# C-10_PMIC.net
KiCad netlist of a schematic drawn in Altium Designer
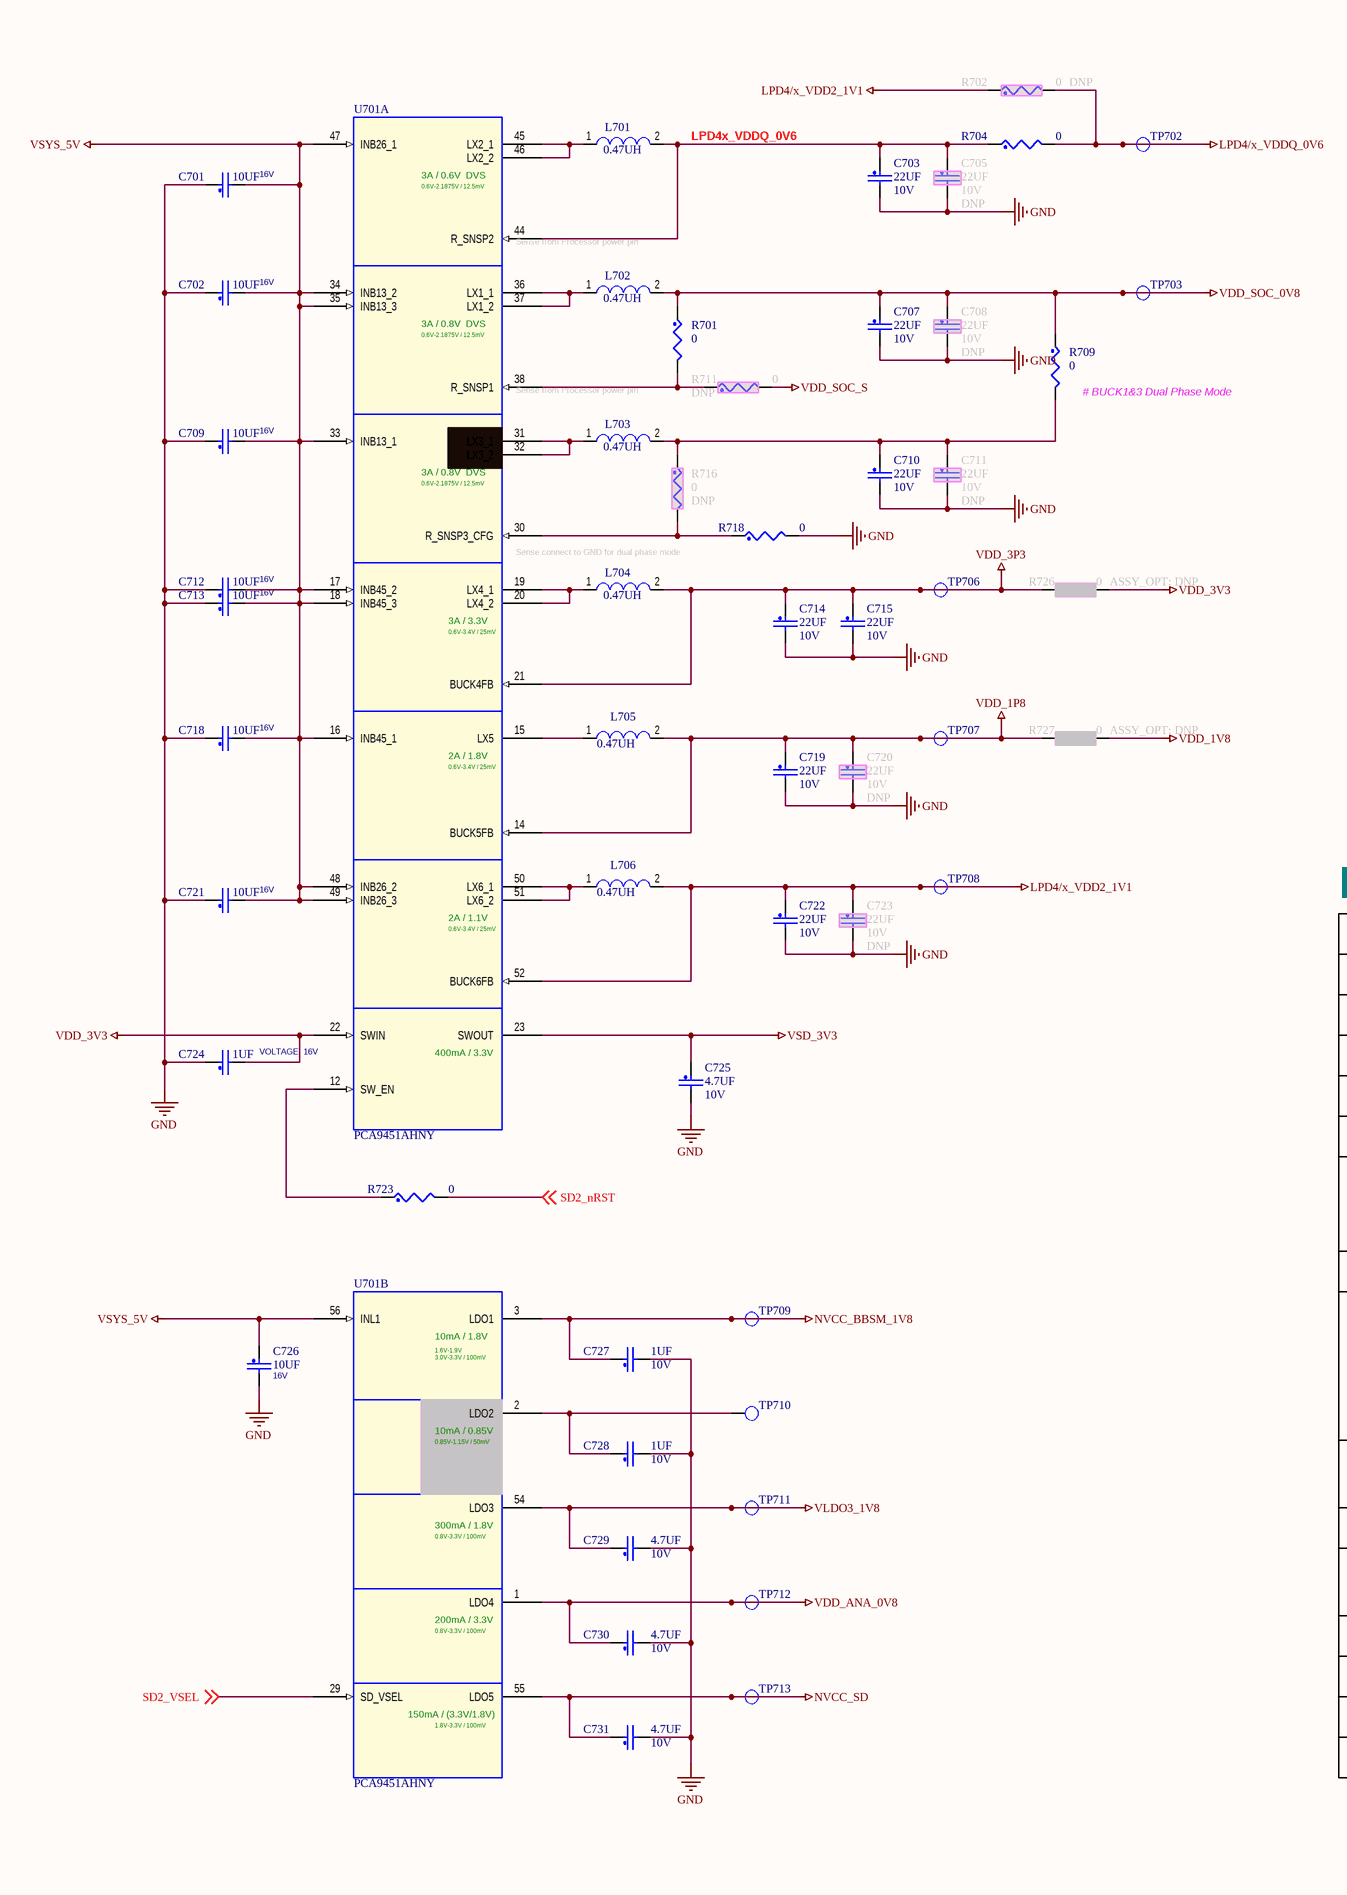
[diagram p0: C-10 PMIC.SchDoc, left]
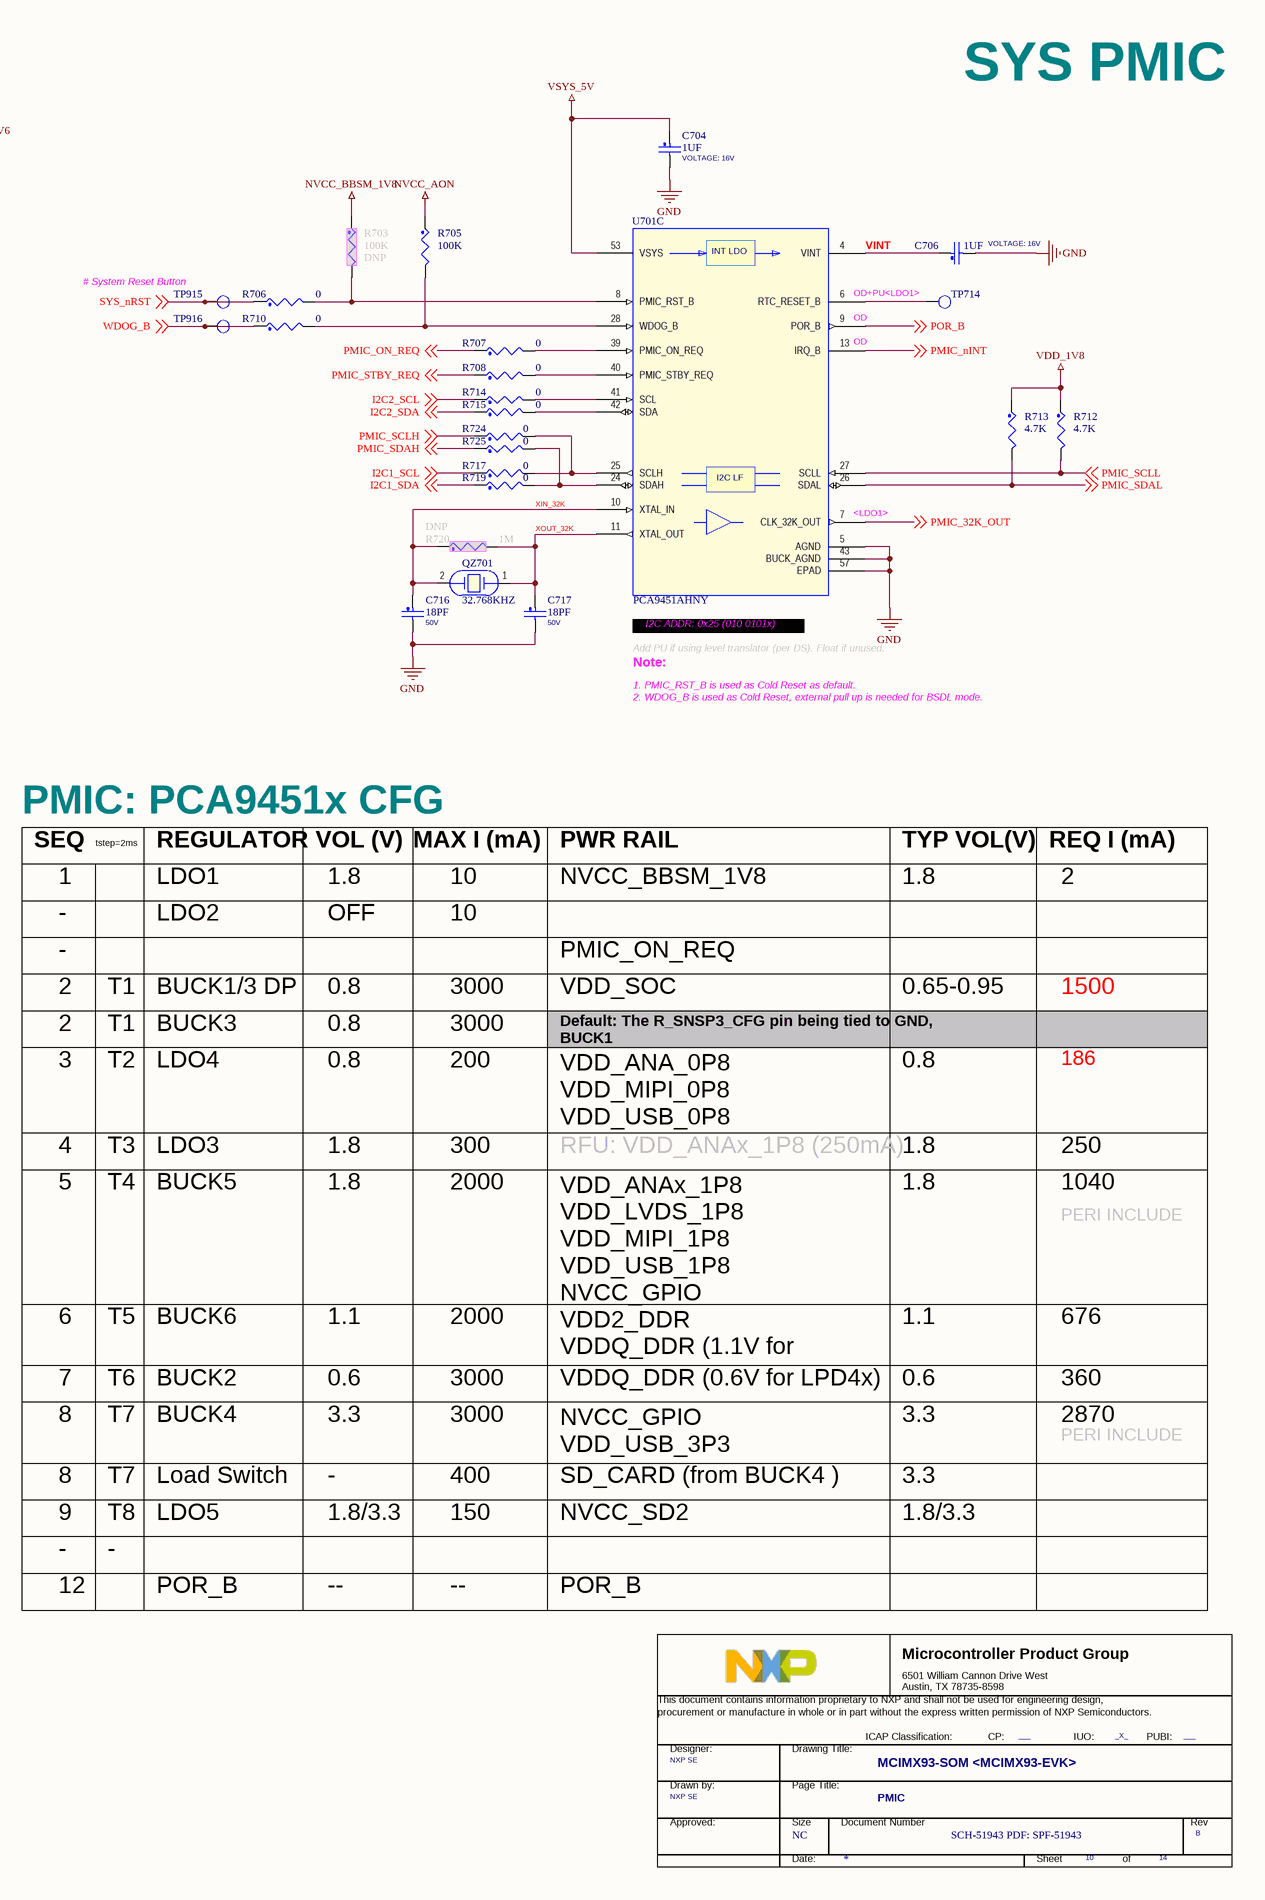
[diagram p1: C-10 PMIC.SchDoc, right]

(export (version "E")
  (design (tool "Eeschema 10.0.6"))
  (components
    (comp (ref "C701")
      (value "10UF")
      (footprint "CC0603")
      (description "CAP CER 10.0uF 16V 10% X5R 0603")
      (fields (field (name "TOLERANCE") "10%") (field (name "VOLTAGE") "16V"))
      (libsource (lib "*") (part "CAP_NP"))
    )
    (comp (ref "C702")
      (value "10UF")
      (footprint "CC0603")
      (description "CAP CER 10.0uF 16V 10% X5R 0603")
      (fields (field (name "VOLTAGE") "16V") (field (name "TOLERANCE") "10%"))
      (libsource (lib "*") (part "CAP_NP"))
    )
    (comp (ref "C703")
      (value "22UF")
      (footprint "CC0603")
      (description "CAP CER 22uF 10V 20% X5R 0603")
      (fields (field (name "VOLTAGE") "10V") (field (name "TOLERANCE") "20%"))
      (libsource (lib "*") (part "CAP_NP"))
    )
    (comp (ref "C704")
      (value "1UF")
      (footprint "0402_CC")
      (description "CAP CER 1uF 16V 10% X5R 0402")
      (fields (field (name "TOLERANCE") "10%") (field (name "VOLTAGE") "16V"))
      (libsource (lib "*") (part "CAP_NP"))
    )
    (comp (ref "C705")
      (value "22UF")
      (footprint "CC0603")
      (description "CAP CER 22uF 10V 20% X5R 0603")
      (fields (field (name "ASSY_OPT") "DNP") (field (name "TOLERANCE") "20%") (field (name "VOLTAGE") "10V"))
      (libsource (lib "*") (part "CAP_NP"))
    )
    (comp (ref "C706")
      (value "1UF")
      (footprint "0402_CC")
      (description "CAP CER 1uF 16V 10% X5R 0402")
      (fields (field (name "VOLTAGE") "16V") (field (name "TOLERANCE") "10%"))
      (libsource (lib "*") (part "CAP_NP"))
    )
    (comp (ref "C707")
      (value "22UF")
      (footprint "CC0603")
      (description "CAP CER 22uF 10V 20% X5R 0603")
      (fields (field (name "TOLERANCE") "20%") (field (name "VOLTAGE") "10V"))
      (libsource (lib "*") (part "CAP_NP"))
    )
    (comp (ref "C708")
      (value "22UF")
      (footprint "CC0603")
      (description "CAP CER 22uF 10V 20% X5R 0603")
      (fields (field (name "ASSY_OPT") "DNP") (field (name "VOLTAGE") "10V") (field (name "TOLERANCE") "20%"))
      (libsource (lib "*") (part "CAP_NP"))
    )
    (comp (ref "C709")
      (value "10UF")
      (footprint "CC0603")
      (description "CAP CER 10.0uF 16V 10% X5R 0603")
      (fields (field (name "VOLTAGE") "16V") (field (name "TOLERANCE") "10%"))
      (libsource (lib "*") (part "CAP_NP"))
    )
    (comp (ref "C710")
      (value "22UF")
      (footprint "CC0603")
      (description "CAP CER 22uF 10V 20% X5R 0603")
      (fields (field (name "VOLTAGE") "10V") (field (name "TOLERANCE") "20%"))
      (libsource (lib "*") (part "CAP_NP"))
    )
    (comp (ref "C711")
      (value "22UF")
      (footprint "CC0603")
      (description "CAP CER 22uF 10V 20% X5R 0603")
      (fields (field (name "ASSY_OPT") "DNP") (field (name "TOLERANCE") "20%") (field (name "VOLTAGE") "10V"))
      (libsource (lib "*") (part "CAP_NP"))
    )
    (comp (ref "C712")
      (value "10UF")
      (footprint "CC0603")
      (description "CAP CER 10.0uF 16V 10% X5R 0603")
      (fields (field (name "TOLERANCE") "10%") (field (name "VOLTAGE") "16V"))
      (libsource (lib "*") (part "CAP_NP"))
    )
    (comp (ref "C713")
      (value "10UF")
      (footprint "CC0603")
      (description "CAP CER 10.0uF 16V 10% X5R 0603")
      (fields (field (name "VOLTAGE") "16V") (field (name "TOLERANCE") "10%"))
      (libsource (lib "*") (part "CAP_NP"))
    )
    (comp (ref "C714")
      (value "22UF")
      (footprint "CC0603")
      (description "CAP CER 22uF 10V 20% X5R 0603")
      (fields (field (name "VOLTAGE") "10V") (field (name "TOLERANCE") "20%"))
      (libsource (lib "*") (part "CAP_NP"))
    )
    (comp (ref "C715")
      (value "22UF")
      (footprint "CC0603")
      (description "CAP CER 22uF 10V 20% X5R 0603")
      (fields (field (name "VOLTAGE") "10V") (field (name "TOLERANCE") "20%"))
      (libsource (lib "*") (part "CAP_NP"))
    )
    (comp (ref "C716")
      (value "18PF")
      (footprint "0201_CC")
      (description "CAP CER 18pF 50V 5% C0G 0201")
      (fields (field (name "TOLERANCE") "5%") (field (name "VOLTAGE") "50V"))
      (libsource (lib "*") (part "CAP_NP"))
    )
    (comp (ref "C717")
      (value "18PF")
      (footprint "0201_CC")
      (description "CAP CER 18pF 50V 5% C0G 0201")
      (fields (field (name "TOLERANCE") "5%") (field (name "VOLTAGE") "50V"))
      (libsource (lib "*") (part "CAP_NP"))
    )
    (comp (ref "C718")
      (value "10UF")
      (footprint "CC0603")
      (description "CAP CER 10.0uF 16V 10% X5R 0603")
      (fields (field (name "TOLERANCE") "10%") (field (name "VOLTAGE") "16V"))
      (libsource (lib "*") (part "CAP_NP"))
    )
    (comp (ref "C719")
      (value "22UF")
      (footprint "CC0603")
      (description "CAP CER 22uF 10V 20% X5R 0603")
      (fields (field (name "VOLTAGE") "10V") (field (name "TOLERANCE") "20%"))
      (libsource (lib "*") (part "CAP_NP"))
    )
    (comp (ref "C720")
      (value "22UF")
      (footprint "CC0603")
      (description "CAP CER 22uF 10V 20% X5R 0603")
      (fields (field (name "ASSY_OPT") "DNP") (field (name "VOLTAGE") "10V") (field (name "TOLERANCE") "20%"))
      (libsource (lib "*") (part "CAP_NP"))
    )
    (comp (ref "C721")
      (value "10UF")
      (footprint "CC0603")
      (description "CAP CER 10.0uF 16V 10% X5R 0603")
      (fields (field (name "TOLERANCE") "10%") (field (name "VOLTAGE") "16V"))
      (libsource (lib "*") (part "CAP_NP"))
    )
    (comp (ref "C722")
      (value "22UF")
      (footprint "CC0603")
      (description "CAP CER 22uF 10V 20% X5R 0603")
      (fields (field (name "VOLTAGE") "10V") (field (name "TOLERANCE") "20%"))
      (libsource (lib "*") (part "CAP_NP"))
    )
    (comp (ref "C723")
      (value "22UF")
      (footprint "CC0603")
      (description "CAP CER 22uF 10V 20% X5R 0603")
      (fields (field (name "ASSY_OPT") "DNP") (field (name "TOLERANCE") "20%") (field (name "VOLTAGE") "10V"))
      (libsource (lib "*") (part "CAP_NP"))
    )
    (comp (ref "C724")
      (value "1UF")
      (footprint "0402_CC")
      (description "CAP CER 1uF 16V 10% X5R 0402")
      (fields (field (name "TOLERANCE") "10%") (field (name "VOLTAGE") "16V"))
      (libsource (lib "*") (part "CAP_NP"))
    )
    (comp (ref "C725")
      (value "4.7UF")
      (footprint "cc0402_tol0p15")
      (description "CAP CER 4.7uF 10V 10% X5R 0402")
      (fields (field (name "TOLERANCE") "10%") (field (name "VOLTAGE") "10V"))
      (libsource (lib "*") (part "CAP_NP"))
    )
    (comp (ref "C726")
      (value "10UF")
      (footprint "CC0603")
      (description "CAP CER 10.0uF 16V 10% X5R 0603")
      (fields (field (name "TOLERANCE") "10%") (field (name "VOLTAGE") "16V"))
      (libsource (lib "*") (part "CAP_NP"))
    )
    (comp (ref "C727")
      (value "1UF")
      (footprint "0201_CC")
      (description "CAP CER 1.0uF 10V 10% X5R 0201")
      (fields (field (name "VOLTAGE") "10V") (field (name "TOLERANCE") "10%"))
      (libsource (lib "*") (part "CAP_NP"))
    )
    (comp (ref "C728")
      (value "1UF")
      (footprint "0201_CC")
      (description "CAP CER 1.0uF 10V 10% X5R 0201")
      (fields (field (name "VOLTAGE") "10V") (field (name "TOLERANCE") "10%"))
      (libsource (lib "*") (part "CAP_NP"))
    )
    (comp (ref "C729")
      (value "4.7UF")
      (footprint "cc0402_tol0p15")
      (description "CAP CER 4.7uF 10V 10% X5R 0402")
      (fields (field (name "VOLTAGE") "10V") (field (name "TOLERANCE") "10%"))
      (libsource (lib "*") (part "CAP_NP"))
    )
    (comp (ref "C730")
      (value "4.7UF")
      (footprint "cc0402_tol0p15")
      (description "CAP CER 4.7uF 10V 10% X5R 0402")
      (fields (field (name "VOLTAGE") "10V") (field (name "TOLERANCE") "10%"))
      (libsource (lib "*") (part "CAP_NP"))
    )
    (comp (ref "C731")
      (value "4.7UF")
      (footprint "cc0402_tol0p15")
      (description "CAP CER 4.7uF 10V 10% X5R 0402")
      (fields (field (name "VOLTAGE") "10V") (field (name "TOLERANCE") "10%"))
      (libsource (lib "*") (part "CAP_NP"))
    )
    (comp (ref "L701")
      (value "0.47UH")
      (footprint "ind_sph2520")
      (description "IND PWR 0.47uH@1MHZ 4.7A 20% SMT")
      (fields (field (name "TOLERANCE") "20%"))
      (libsource (lib "*") (part "INDUCTOR"))
    )
    (comp (ref "L702")
      (value "0.47UH")
      (footprint "ind_sph2520")
      (description "IND PWR 0.47uH@1MHZ 4.7A 20% SMT")
      (fields (field (name "TOLERANCE") "20%"))
      (libsource (lib "*") (part "INDUCTOR"))
    )
    (comp (ref "L703")
      (value "0.47UH")
      (footprint "ind_sph2520")
      (description "IND PWR 0.47uH@1MHZ 4.7A 20% SMT")
      (fields (field (name "TOLERANCE") "20%"))
      (libsource (lib "*") (part "INDUCTOR"))
    )
    (comp (ref "L704")
      (value "0.47UH")
      (footprint "ind_sph2520")
      (description "IND PWR 0.47uH@1MHZ 4.7A 20% SMT")
      (fields (field (name "TOLERANCE") "20%"))
      (libsource (lib "*") (part "INDUCTOR"))
    )
    (comp (ref "L705")
      (value "0.47UH")
      (footprint "IND_2016A")
      (description "IND PWR 0.47uH@1MHz 3.4A 20% 2016")
      (fields (field (name "TOLERANCE") "20%"))
      (libsource (lib "*") (part "INDUCTOR"))
    )
    (comp (ref "L706")
      (value "0.47UH")
      (footprint "IND_2016A")
      (description "IND PWR 0.47uH@1MHz 3.4A 20% 2016")
      (fields (field (name "TOLERANCE") "20%"))
      (libsource (lib "*") (part "INDUCTOR"))
    )
    (comp (ref "QZ701")
      (value "32.768KHZ")
      (footprint "XTAL2-3P2X1P5-SM")
      (description "XTAL 32.768KHZ 12.5PF 20PPM 3.2X1.5MM SMT")
      (libsource (lib "*") (part "XTAL"))
    )
    (comp (ref "R701")
      (value "0")
      (footprint "0402_CC")
      (description "RES MF ZERO OHM 1/16W 5% 0402")
      (fields (field (name "VOLTAGE") "1/16W") (field (name "TOLERANCE") "5%"))
      (libsource (lib "*") (part "RES"))
    )
    (comp (ref "R702")
      (value "0")
      (footprint "0603_CC")
      (description "RES MF ZERO OHM 1/10W -- 0603")
      (fields (field (name "ASSY_OPT") "DNP"))
      (libsource (lib "*") (part "RES"))
    )
    (comp (ref "R703")
      (value "100K")
      (footprint "0402_CC")
      (description "RES MF 100K 1/16W 5% 0402")
      (fields (field (name "ASSY_OPT") "DNP") (field (name "TOLERANCE") "5%") (field (name "VOLTAGE") "50V"))
      (libsource (lib "*") (part "RES"))
    )
    (comp (ref "R704")
      (value "0")
      (footprint "0603_CC")
      (description "RES MF ZERO OHM 1/10W -- 0603")
      (libsource (lib "*") (part "RES"))
    )
    (comp (ref "R705")
      (value "100K")
      (footprint "0402_CC")
      (description "RES MF 100K 1/16W 5% 0402")
      (fields (field (name "VOLTAGE") "50V") (field (name "TOLERANCE") "5%"))
      (libsource (lib "*") (part "RES"))
    )
    (comp (ref "R706")
      (value "0")
      (footprint "0402_CC")
      (description "RES MF ZERO OHM 1/16W 5% 0402")
      (fields (field (name "VOLTAGE") "1/16W") (field (name "TOLERANCE") "5%"))
      (libsource (lib "*") (part "RES"))
    )
    (comp (ref "R707")
      (value "0")
      (footprint "0402_CC")
      (description "RES MF ZERO OHM 1/16W 5% 0402")
      (fields (field (name "TOLERANCE") "5%") (field (name "VOLTAGE") "1/16W"))
      (libsource (lib "*") (part "RES"))
    )
    (comp (ref "R708")
      (value "0")
      (footprint "0402_CC")
      (description "RES MF ZERO OHM 1/16W 5% 0402")
      (fields (field (name "VOLTAGE") "1/16W") (field (name "TOLERANCE") "5%"))
      (libsource (lib "*") (part "RES"))
    )
    (comp (ref "R709")
      (value "0")
      (footprint "0603_CC")
      (description "RES MF ZERO OHM 1/10W -- 0603")
      (libsource (lib "*") (part "RES"))
    )
    (comp (ref "R710")
      (value "0")
      (footprint "0402_CC")
      (description "RES MF ZERO OHM 1/16W 5% 0402")
      (fields (field (name "VOLTAGE") "1/16W") (field (name "TOLERANCE") "5%"))
      (libsource (lib "*") (part "RES"))
    )
    (comp (ref "R711")
      (value "0")
      (footprint "0402_CC")
      (description "RES MF ZERO OHM 1/16W 5% 0402")
      (fields
        (field (name "ASSY_OPT") "DNP")
        (field (name "TOLERANCE") "5%")
        (field (name "VOLTAGE") "1/16W")
      )
      (libsource (lib "*") (part "RES"))
    )
    (comp (ref "R712")
      (value "4.7K")
      (footprint "0402_CC")
      (description "RES MF 4.7K 1/10W 5% AEC-Q200 0402")
      (fields (field (name "TOLERANCE") "5%") (field (name "VOLTAGE") "50V"))
      (libsource (lib "*") (part "RES"))
    )
    (comp (ref "R713")
      (value "4.7K")
      (footprint "0402_CC")
      (description "RES MF 4.7K 1/10W 5% AEC-Q200 0402")
      (fields (field (name "VOLTAGE") "50V") (field (name "TOLERANCE") "5%"))
      (libsource (lib "*") (part "RES"))
    )
    (comp (ref "R714")
      (value "0")
      (footprint "0402_CC")
      (description "RES MF ZERO OHM 1/16W 5% 0402")
      (fields (field (name "TOLERANCE") "5%") (field (name "VOLTAGE") "1/16W"))
      (libsource (lib "*") (part "RES"))
    )
    (comp (ref "R715")
      (value "0")
      (footprint "0402_CC")
      (description "RES MF ZERO OHM 1/16W 5% 0402")
      (fields (field (name "TOLERANCE") "5%") (field (name "VOLTAGE") "1/16W"))
      (libsource (lib "*") (part "RES"))
    )
    (comp (ref "R716")
      (value "0")
      (footprint "0402_CC")
      (description "RES MF ZERO OHM 1/16W 5% 0402")
      (fields
        (field (name "ASSY_OPT") "DNP")
        (field (name "TOLERANCE") "5%")
        (field (name "VOLTAGE") "1/16W")
      )
      (libsource (lib "*") (part "RES"))
    )
    (comp (ref "R717")
      (value "0")
      (footprint "0201_CC")
      (description "RES MF ZERO OHM 1/20W -- 0201")
      (libsource (lib "*") (part "RES"))
    )
    (comp (ref "R718")
      (value "0")
      (footprint "0402_CC")
      (description "RES MF ZERO OHM 1/16W 5% 0402")
      (fields (field (name "TOLERANCE") "5%") (field (name "VOLTAGE") "1/16W"))
      (libsource (lib "*") (part "RES"))
    )
    (comp (ref "R719")
      (value "0")
      (footprint "0201_CC")
      (description "RES MF ZERO OHM 1/20W -- 0201")
      (libsource (lib "*") (part "RES"))
    )
    (comp (ref "R720")
      (value "1M")
      (footprint "0201_CC")
      (description "RES MF 1.0M 1/20W 5% AEC-Q200 0201")
      (fields (field (name "ASSY_OPT") "DNP") (field (name "TOLERANCE") "5%") (field (name "VOLTAGE") "25V"))
      (libsource (lib "*") (part "RES"))
    )
    (comp (ref "R723")
      (value "0")
      (footprint "0402_CC")
      (description "RES MF ZERO OHM 1/16W 5% 0402")
      (fields (field (name "TOLERANCE") "5%") (field (name "VOLTAGE") "1/16W"))
      (libsource (lib "*") (part "RES"))
    )
    (comp (ref "R724")
      (value "0")
      (footprint "0201_CC")
      (description "RES MF ZERO OHM 1/20W -- 0201")
      (libsource (lib "*") (part "RES"))
    )
    (comp (ref "R725")
      (value "0")
      (footprint "0201_CC")
      (description "RES MF ZERO OHM 1/20W -- 0201")
      (libsource (lib "*") (part "RES"))
    )
    (comp (ref "R726")
      (value "0")
      (footprint "RC0805_OV")
      (description "RES MF ZERO OHM 1/8W -- 0805")
      (fields (field (name "ASSY_OPT") "DNP") (field (name "TOLERANCE") "5%"))
      (libsource (lib "*") (part "RES"))
    )
    (comp (ref "R727")
      (value "0")
      (footprint "RC0805_OV")
      (description "RES MF ZERO OHM 1/8W -- 0805")
      (fields (field (name "ASSY_OPT") "DNP") (field (name "TOLERANCE") "5%"))
      (libsource (lib "*") (part "RES"))
    )
    (comp (ref "TP702")
      (value "TP_35MIL")
      (footprint "testpoint_35mil")
      (description "TEST POINT PAD .035 SMT, no part to order")
      (libsource (lib "*") (part "T POINT R"))
    )
    (comp (ref "TP703")
      (value "TP_35MIL")
      (footprint "testpoint_35mil")
      (description "TEST POINT PAD .035 SMT, no part to order")
      (libsource (lib "*") (part "T POINT R"))
    )
    (comp (ref "TP706")
      (value "TP_35MIL")
      (footprint "testpoint_35mil")
      (description "TEST POINT PAD .035 SMT, no part to order")
      (libsource (lib "*") (part "T POINT R"))
    )
    (comp (ref "TP707")
      (value "TP_35MIL")
      (footprint "testpoint_35mil")
      (description "TEST POINT PAD .035 SMT, no part to order")
      (libsource (lib "*") (part "T POINT R"))
    )
    (comp (ref "TP708")
      (value "TP_35MIL")
      (footprint "testpoint_35mil")
      (description "TEST POINT PAD .035 SMT, no part to order")
      (libsource (lib "*") (part "T POINT R"))
    )
    (comp (ref "TP709")
      (value "TP_35MIL")
      (footprint "testpoint_35mil")
      (description "TEST POINT PAD .035 SMT, no part to order")
      (libsource (lib "*") (part "T POINT R"))
    )
    (comp (ref "TP710")
      (value "TP_35MIL")
      (footprint "testpoint_35mil")
      (description "TEST POINT PAD .035 SMT, no part to order")
      (libsource (lib "*") (part "T POINT R"))
    )
    (comp (ref "TP711")
      (value "TP_35MIL")
      (footprint "testpoint_35mil")
      (description "TEST POINT PAD .035 SMT, no part to order")
      (libsource (lib "*") (part "T POINT R"))
    )
    (comp (ref "TP712")
      (value "TP_35MIL")
      (footprint "testpoint_35mil")
      (description "TEST POINT PAD .035 SMT, no part to order")
      (libsource (lib "*") (part "T POINT R"))
    )
    (comp (ref "TP713")
      (value "TP_35MIL")
      (footprint "testpoint_35mil")
      (description "TEST POINT PAD .035 SMT, no part to order")
      (libsource (lib "*") (part "T POINT R"))
    )
    (comp (ref "TP714")
      (value "TP_35MIL")
      (footprint "testpoint_35mil")
      (description "TEST POINT PAD .035 SMT, no part to order")
      (libsource (lib "*") (part "T POINT R"))
    )
    (comp (ref "TP915")
      (value "TP_35MIL")
      (footprint "testpoint_35mil")
      (description "TEST POINT PAD .035 SMT, no part to order")
      (libsource (lib "*") (part "T POINT R"))
    )
    (comp (ref "TP916")
      (value "TP_35MIL")
      (footprint "testpoint_35mil")
      (description "TEST POINT PAD .035 SMT, no part to order")
      (libsource (lib "*") (part "T POINT R"))
    )
    (comp (ref "U701")
      (value "PCA9451AHNY")
      (footprint "hvqfn56_0p4_7x7_ep4p7mm")
      (description "IC POWER MANAGEMENT 2.7-5.5V HVQFN56")
      (libsource (lib "*") (part "PCA9451AHNY"))
    )
  )
  (nets
    (net (code "1") (name "/LPD4x_VDDQ_0V6") (class "Default")
      (node (ref "C703") (pin "1") (pinfunction "1_1") (pintype "passive"))
      (node (ref "C705") (pin "1") (pinfunction "1_1") (pintype "passive"))
      (node (ref "L701") (pin "2") (pinfunction "2_2") (pintype "passive"))
      (node (ref "R704") (pin "1") (pinfunction "1_1") (pintype "passive"))
      (node (ref "U701") (pin "44") (pinfunction "R_SNSP2_44") (pintype "input"))
    )
    (net (code "2") (name "/VINT") (class "Default")
      (node (ref "C706") (pin "1") (pinfunction "1_1") (pintype "passive"))
      (node (ref "U701") (pin "4") (pinfunction "VINT_4") (pintype "output"))
    )
    (net (code "3") (name "/XIN_32K") (class "Default")
      (node (ref "C716") (pin "1") (pinfunction "1_1") (pintype "passive"))
      (node (ref "QZ701") (pin "2") (pinfunction "2_2") (pintype "passive"))
      (node (ref "R720") (pin "1") (pinfunction "1_1") (pintype "passive"))
      (node (ref "U701") (pin "10") (pinfunction "XTAL_IN_10") (pintype "input"))
    )
    (net (code "4") (name "/XOUT_32K") (class "Default")
      (node (ref "C717") (pin "1") (pinfunction "1_1") (pintype "passive"))
      (node (ref "QZ701") (pin "1") (pinfunction "1_1") (pintype "passive"))
      (node (ref "R720") (pin "2") (pinfunction "2_2") (pintype "passive"))
      (node (ref "U701") (pin "11") (pinfunction "XTAL_OUT_11") (pintype "output"))
    )
    (net (code "5") (name "GND") (class "Default")
      (node (ref "C701") (pin "1") (pinfunction "1_1") (pintype "passive"))
      (node (ref "C702") (pin "1") (pinfunction "1_1") (pintype "passive"))
      (node (ref "C703") (pin "2") (pinfunction "2_2") (pintype "passive"))
      (node (ref "C704") (pin "2") (pinfunction "2_2") (pintype "passive"))
      (node (ref "C705") (pin "2") (pinfunction "2_2") (pintype "passive"))
      (node (ref "C706") (pin "2") (pinfunction "2_2") (pintype "passive"))
      (node (ref "C707") (pin "2") (pinfunction "2_2") (pintype "passive"))
      (node (ref "C708") (pin "2") (pinfunction "2_2") (pintype "passive"))
      (node (ref "C709") (pin "1") (pinfunction "1_1") (pintype "passive"))
      (node (ref "C710") (pin "2") (pinfunction "2_2") (pintype "passive"))
      (node (ref "C711") (pin "2") (pinfunction "2_2") (pintype "passive"))
      (node (ref "C712") (pin "1") (pinfunction "1_1") (pintype "passive"))
      (node (ref "C713") (pin "1") (pinfunction "1_1") (pintype "passive"))
      (node (ref "C714") (pin "2") (pinfunction "2_2") (pintype "passive"))
      (node (ref "C715") (pin "2") (pinfunction "2_2") (pintype "passive"))
      (node (ref "C716") (pin "2") (pinfunction "2_2") (pintype "passive"))
      (node (ref "C717") (pin "2") (pinfunction "2_2") (pintype "passive"))
      (node (ref "C718") (pin "1") (pinfunction "1_1") (pintype "passive"))
      (node (ref "C719") (pin "2") (pinfunction "2_2") (pintype "passive"))
      (node (ref "C720") (pin "2") (pinfunction "2_2") (pintype "passive"))
      (node (ref "C721") (pin "1") (pinfunction "1_1") (pintype "passive"))
      (node (ref "C722") (pin "2") (pinfunction "2_2") (pintype "passive"))
      (node (ref "C723") (pin "2") (pinfunction "2_2") (pintype "passive"))
      (node (ref "C724") (pin "1") (pinfunction "1_1") (pintype "passive"))
      (node (ref "C725") (pin "2") (pinfunction "2_2") (pintype "passive"))
      (node (ref "C726") (pin "2") (pinfunction "2_2") (pintype "passive"))
      (node (ref "C727") (pin "2") (pinfunction "2_2") (pintype "passive"))
      (node (ref "C728") (pin "2") (pinfunction "2_2") (pintype "passive"))
      (node (ref "C729") (pin "2") (pinfunction "2_2") (pintype "passive"))
      (node (ref "C730") (pin "2") (pinfunction "2_2") (pintype "passive"))
      (node (ref "C731") (pin "2") (pinfunction "2_2") (pintype "passive"))
      (node (ref "R718") (pin "2") (pinfunction "2_2") (pintype "passive"))
      (node (ref "U701") (pin "43") (pinfunction "BUCK_AGND_43") (pintype "power_in"))
      (node (ref "U701") (pin "5") (pinfunction "AGND_5") (pintype "power_in"))
      (node (ref "U701") (pin "57") (pinfunction "EPAD_57") (pintype "power_in"))
    )
    (net (code "6") (name "I2C1_SCL") (class "Default")
      (node (ref "R717") (pin "1") (pinfunction "1_1") (pintype "passive"))
    )
    (net (code "7") (name "I2C1_SDA") (class "Default")
      (node (ref "R719") (pin "1") (pinfunction "1_1") (pintype "passive"))
    )
    (net (code "8") (name "I2C2_SCL") (class "Default")
      (node (ref "R714") (pin "1") (pinfunction "1_1") (pintype "passive"))
    )
    (net (code "9") (name "I2C2_SDA") (class "Default")
      (node (ref "R715") (pin "1") (pinfunction "1_1") (pintype "passive"))
    )
    (net (code "10") (name "LPD4{slash}x_VDD2_1V1") (class "Default")
      (node (ref "C722") (pin "1") (pinfunction "1_1") (pintype "passive"))
      (node (ref "C723") (pin "1") (pinfunction "1_1") (pintype "passive"))
      (node (ref "L706") (pin "2") (pinfunction "2_2") (pintype "passive"))
      (node (ref "R702") (pin "1") (pinfunction "1_1") (pintype "passive"))
      (node (ref "TP708") (pin "1") (pinfunction "TP_1") (pintype "passive"))
      (node (ref "U701") (pin "52") (pinfunction "BUCK6FB_52") (pintype "input"))
    )
    (net (code "11") (name "LPD4{slash}x_VDDQ_0V6") (class "Default")
      (node (ref "R702") (pin "2") (pinfunction "2_2") (pintype "passive"))
      (node (ref "R704") (pin "2") (pinfunction "2_2") (pintype "passive"))
      (node (ref "TP702") (pin "1") (pinfunction "TP_1") (pintype "passive"))
    )
    (net (code "12") (name "NVCC_AON") (class "Default")
      (node (ref "R705") (pin "1") (pinfunction "1_1") (pintype "passive"))
    )
    (net (code "13") (name "NVCC_BBSM_1V8") (class "Default")
      (node (ref "C727") (pin "1") (pinfunction "1_1") (pintype "passive"))
      (node (ref "R703") (pin "1") (pinfunction "1_1") (pintype "passive"))
      (node (ref "TP709") (pin "1") (pinfunction "TP_1") (pintype "passive"))
      (node (ref "U701") (pin "3") (pinfunction "LDO1_3") (pintype "output"))
    )
    (net (code "14") (name "NVCC_SD") (class "Default")
      (node (ref "C731") (pin "1") (pinfunction "1_1") (pintype "passive"))
      (node (ref "TP713") (pin "1") (pinfunction "TP_1") (pintype "passive"))
      (node (ref "U701") (pin "55") (pinfunction "LDO5_55") (pintype "output"))
    )
    (net (code "15") (name "Net-(C710-Pad1)") (class "Default")
      (node (ref "C710") (pin "1") (pinfunction "1_1") (pintype "passive"))
      (node (ref "C711") (pin "1") (pinfunction "1_1") (pintype "passive"))
      (node (ref "L703") (pin "2") (pinfunction "2_2") (pintype "passive"))
      (node (ref "R709") (pin "2") (pinfunction "2_2") (pintype "passive"))
      (node (ref "R716") (pin "1") (pinfunction "1_1") (pintype "passive"))
    )
    (net (code "16") (name "Net-(TP710-TP)") (class "Default")
      (node (ref "C728") (pin "1") (pinfunction "1_1") (pintype "passive"))
      (node (ref "TP710") (pin "1") (pinfunction "TP_1") (pintype "passive"))
      (node (ref "U701") (pin "2") (pinfunction "LDO2_2") (pintype "output"))
    )
    (net (code "17") (name "Net-(TP714-TP)") (class "Default")
      (node (ref "TP714") (pin "1") (pinfunction "TP_1") (pintype "passive"))
      (node (ref "U701") (pin "6") (pinfunction "RTC_RESET_B_6") (pintype "open_collector"))
    )
    (net (code "18") (name "Net-(U701A-LX1_1)") (class "Default")
      (node (ref "L702") (pin "1") (pinfunction "1_1") (pintype "passive"))
      (node (ref "U701") (pin "36") (pinfunction "LX1_1_36") (pintype "power_in"))
      (node (ref "U701") (pin "37") (pinfunction "LX1_2_37") (pintype "power_in"))
    )
    (net (code "19") (name "Net-(U701A-LX2_1)") (class "Default")
      (node (ref "L701") (pin "1") (pinfunction "1_1") (pintype "passive"))
      (node (ref "U701") (pin "45") (pinfunction "LX2_1_45") (pintype "power_in"))
      (node (ref "U701") (pin "46") (pinfunction "LX2_2_46") (pintype "power_in"))
    )
    (net (code "20") (name "Net-(U701A-LX3_1)") (class "Default")
      (node (ref "L703") (pin "1") (pinfunction "1_1") (pintype "passive"))
      (node (ref "U701") (pin "31") (pinfunction "LX3_1_31") (pintype "power_in"))
      (node (ref "U701") (pin "32") (pinfunction "LX3_2_32") (pintype "power_in"))
    )
    (net (code "21") (name "Net-(U701A-LX4_1)") (class "Default")
      (node (ref "L704") (pin "1") (pinfunction "1_1") (pintype "passive"))
      (node (ref "U701") (pin "19") (pinfunction "LX4_1_19") (pintype "power_in"))
      (node (ref "U701") (pin "20") (pinfunction "LX4_2_20") (pintype "power_in"))
    )
    (net (code "22") (name "Net-(U701A-LX5)") (class "Default")
      (node (ref "L705") (pin "1") (pinfunction "1_1") (pintype "passive"))
      (node (ref "U701") (pin "15") (pinfunction "LX5_15") (pintype "power_in"))
    )
    (net (code "23") (name "Net-(U701A-LX6_1)") (class "Default")
      (node (ref "L706") (pin "1") (pinfunction "1_1") (pintype "passive"))
      (node (ref "U701") (pin "50") (pinfunction "LX6_1_50") (pintype "power_in"))
      (node (ref "U701") (pin "51") (pinfunction "LX6_2_51") (pintype "power_in"))
    )
    (net (code "24") (name "Net-(U701A-R_SNSP1)") (class "Default")
      (node (ref "R701") (pin "2") (pinfunction "2_2") (pintype "passive"))
      (node (ref "R711") (pin "1") (pinfunction "1_1") (pintype "passive"))
      (node (ref "U701") (pin "38") (pinfunction "R_SNSP1_38") (pintype "input"))
    )
    (net (code "25") (name "Net-(U701A-R_SNSP3_CFG)") (class "Default")
      (node (ref "R716") (pin "2") (pinfunction "2_2") (pintype "passive"))
      (node (ref "R718") (pin "1") (pinfunction "1_1") (pintype "passive"))
      (node (ref "U701") (pin "30") (pinfunction "R_SNSP3_CFG_30") (pintype "input"))
    )
    (net (code "26") (name "Net-(U701A-SW_EN)") (class "Default")
      (node (ref "R723") (pin "1") (pinfunction "1_1") (pintype "passive"))
      (node (ref "U701") (pin "12") (pinfunction "SW_EN_12") (pintype "input"))
    )
    (net (code "27") (name "Net-(U701C-PMIC_ON_REQ)") (class "Default")
      (node (ref "R707") (pin "2") (pinfunction "2_2") (pintype "passive"))
      (node (ref "U701") (pin "39") (pinfunction "PMIC_ON_REQ_39") (pintype "input"))
    )
    (net (code "28") (name "Net-(U701C-PMIC_RST_B)") (class "Default")
      (node (ref "R703") (pin "2") (pinfunction "2_2") (pintype "passive"))
      (node (ref "R706") (pin "2") (pinfunction "2_2") (pintype "passive"))
      (node (ref "U701") (pin "8") (pinfunction "PMIC_RST_B_8") (pintype "input"))
    )
    (net (code "29") (name "Net-(U701C-PMIC_STBY_REQ)") (class "Default")
      (node (ref "R708") (pin "2") (pinfunction "2_2") (pintype "passive"))
      (node (ref "U701") (pin "40") (pinfunction "PMIC_STBY_REQ_40") (pintype "input"))
    )
    (net (code "30") (name "Net-(U701C-SCL)") (class "Default")
      (node (ref "R714") (pin "2") (pinfunction "2_2") (pintype "passive"))
      (node (ref "U701") (pin "41") (pinfunction "SCL_41") (pintype "input"))
    )
    (net (code "31") (name "Net-(U701C-SCLH)") (class "Default")
      (node (ref "R717") (pin "2") (pinfunction "2_2") (pintype "passive"))
      (node (ref "R724") (pin "2") (pinfunction "2_2") (pintype "passive"))
      (node (ref "U701") (pin "25") (pinfunction "SCLH_25") (pintype "output"))
    )
    (net (code "32") (name "Net-(U701C-SDA)") (class "Default")
      (node (ref "R715") (pin "2") (pinfunction "2_2") (pintype "passive"))
      (node (ref "U701") (pin "42") (pinfunction "SDA_42") (pintype "bidirectional"))
    )
    (net (code "33") (name "Net-(U701C-SDAH)") (class "Default")
      (node (ref "R719") (pin "2") (pinfunction "2_2") (pintype "passive"))
      (node (ref "R725") (pin "2") (pinfunction "2_2") (pintype "passive"))
      (node (ref "U701") (pin "24") (pinfunction "SDAH_24") (pintype "bidirectional"))
    )
    (net (code "34") (name "Net-(U701C-WDOG_B)") (class "Default")
      (node (ref "R705") (pin "2") (pinfunction "2_2") (pintype "passive"))
      (node (ref "R710") (pin "2") (pinfunction "2_2") (pintype "passive"))
      (node (ref "U701") (pin "28") (pinfunction "WDOG_B_28") (pintype "input"))
    )
    (net (code "35") (name "PMIC_32K_OUT") (class "Default")
      (node (ref "U701") (pin "7") (pinfunction "CLK_32K_OUT_7") (pintype "output"))
    )
    (net (code "36") (name "PMIC_ON_REQ") (class "Default")
      (node (ref "R707") (pin "1") (pinfunction "1_1") (pintype "passive"))
    )
    (net (code "37") (name "PMIC_SCLH") (class "Default")
      (node (ref "R724") (pin "1") (pinfunction "1_1") (pintype "passive"))
    )
    (net (code "38") (name "PMIC_SCLL") (class "Default")
      (node (ref "R712") (pin "2") (pinfunction "2_2") (pintype "passive"))
      (node (ref "U701") (pin "27") (pinfunction "SCLL_27") (pintype "input"))
    )
    (net (code "39") (name "PMIC_SDAH") (class "Default")
      (node (ref "R725") (pin "1") (pinfunction "1_1") (pintype "passive"))
    )
    (net (code "40") (name "PMIC_SDAL") (class "Default")
      (node (ref "R713") (pin "2") (pinfunction "2_2") (pintype "passive"))
      (node (ref "U701") (pin "26") (pinfunction "SDAL_26") (pintype "bidirectional"))
    )
    (net (code "41") (name "PMIC_STBY_REQ") (class "Default")
      (node (ref "R708") (pin "1") (pinfunction "1_1") (pintype "passive"))
    )
    (net (code "42") (name "PMIC_nINT") (class "Default")
      (node (ref "U701") (pin "13") (pinfunction "IRQ_B_13") (pintype "open_collector"))
    )
    (net (code "43") (name "POR_B") (class "Default")
      (node (ref "U701") (pin "9") (pinfunction "POR_B_9") (pintype "output"))
    )
    (net (code "44") (name "SD2_VSEL") (class "Default")
      (node (ref "U701") (pin "29") (pinfunction "SD_VSEL_29") (pintype "input"))
    )
    (net (code "45") (name "SD2_nRST") (class "Default")
      (node (ref "R723") (pin "2") (pinfunction "2_2") (pintype "passive"))
    )
    (net (code "46") (name "SYS_nRST") (class "Default")
      (node (ref "R706") (pin "1") (pinfunction "1_1") (pintype "passive"))
      (node (ref "TP915") (pin "1") (pinfunction "TP_1") (pintype "passive"))
    )
    (net (code "47") (name "VDD_1P8") (class "Default")
      (node (ref "C719") (pin "1") (pinfunction "1_1") (pintype "passive"))
      (node (ref "C720") (pin "1") (pinfunction "1_1") (pintype "passive"))
      (node (ref "L705") (pin "2") (pinfunction "2_2") (pintype "passive"))
      (node (ref "R727") (pin "1") (pinfunction "1_1") (pintype "passive"))
      (node (ref "TP707") (pin "1") (pinfunction "TP_1") (pintype "passive"))
      (node (ref "U701") (pin "14") (pinfunction "BUCK5FB_14") (pintype "input"))
    )
    (net (code "48") (name "VDD_1V8") (class "Default")
      (node (ref "R712") (pin "1") (pinfunction "1_1") (pintype "passive"))
      (node (ref "R713") (pin "1") (pinfunction "1_1") (pintype "passive"))
      (node (ref "R727") (pin "2") (pinfunction "2_2") (pintype "passive"))
    )
    (net (code "49") (name "VDD_3P3") (class "Default")
      (node (ref "C714") (pin "1") (pinfunction "1_1") (pintype "passive"))
      (node (ref "C715") (pin "1") (pinfunction "1_1") (pintype "passive"))
      (node (ref "L704") (pin "2") (pinfunction "2_2") (pintype "passive"))
      (node (ref "R726") (pin "1") (pinfunction "1_1") (pintype "passive"))
      (node (ref "TP706") (pin "1") (pinfunction "TP_1") (pintype "passive"))
      (node (ref "U701") (pin "21") (pinfunction "BUCK4FB_21") (pintype "input"))
    )
    (net (code "50") (name "VDD_3V3") (class "Default")
      (node (ref "C724") (pin "2") (pinfunction "2_2") (pintype "passive"))
      (node (ref "R726") (pin "2") (pinfunction "2_2") (pintype "passive"))
      (node (ref "U701") (pin "22") (pinfunction "SWIN_22") (pintype "input"))
    )
    (net (code "51") (name "VDD_ANA_0V8") (class "Default")
      (node (ref "C730") (pin "1") (pinfunction "1_1") (pintype "passive"))
      (node (ref "TP712") (pin "1") (pinfunction "TP_1") (pintype "passive"))
      (node (ref "U701") (pin "1") (pinfunction "LDO4_1") (pintype "output"))
    )
    (net (code "52") (name "VDD_SOC_0V8") (class "Default")
      (node (ref "C707") (pin "1") (pinfunction "1_1") (pintype "passive"))
      (node (ref "C708") (pin "1") (pinfunction "1_1") (pintype "passive"))
      (node (ref "L702") (pin "2") (pinfunction "2_2") (pintype "passive"))
      (node (ref "R701") (pin "1") (pinfunction "1_1") (pintype "passive"))
      (node (ref "R709") (pin "1") (pinfunction "1_1") (pintype "passive"))
      (node (ref "TP703") (pin "1") (pinfunction "TP_1") (pintype "passive"))
    )
    (net (code "53") (name "VDD_SOC_S") (class "Default")
      (node (ref "R711") (pin "2") (pinfunction "2_2") (pintype "passive"))
    )
    (net (code "54") (name "VLDO3_1V8") (class "Default")
      (node (ref "C729") (pin "1") (pinfunction "1_1") (pintype "passive"))
      (node (ref "TP711") (pin "1") (pinfunction "TP_1") (pintype "passive"))
      (node (ref "U701") (pin "54") (pinfunction "LDO3_54") (pintype "output"))
    )
    (net (code "55") (name "VSD_3V3") (class "Default")
      (node (ref "C725") (pin "1") (pinfunction "1_1") (pintype "passive"))
      (node (ref "U701") (pin "23") (pinfunction "SWOUT_23") (pintype "power_in"))
    )
    (net (code "56") (name "VSYS_5V") (class "Default")
      (node (ref "C701") (pin "2") (pinfunction "2_2") (pintype "passive"))
      (node (ref "C702") (pin "2") (pinfunction "2_2") (pintype "passive"))
      (node (ref "C704") (pin "1") (pinfunction "1_1") (pintype "passive"))
      (node (ref "C709") (pin "2") (pinfunction "2_2") (pintype "passive"))
      (node (ref "C712") (pin "2") (pinfunction "2_2") (pintype "passive"))
      (node (ref "C713") (pin "2") (pinfunction "2_2") (pintype "passive"))
      (node (ref "C718") (pin "2") (pinfunction "2_2") (pintype "passive"))
      (node (ref "C721") (pin "2") (pinfunction "2_2") (pintype "passive"))
      (node (ref "C726") (pin "1") (pinfunction "1_1") (pintype "passive"))
      (node (ref "U701") (pin "16") (pinfunction "INB45_1_16") (pintype "input"))
      (node (ref "U701") (pin "17") (pinfunction "INB45_2_17") (pintype "input"))
      (node (ref "U701") (pin "18") (pinfunction "INB45_3_18") (pintype "input"))
      (node (ref "U701") (pin "33") (pinfunction "INB13_1_33") (pintype "input"))
      (node (ref "U701") (pin "34") (pinfunction "INB13_2_34") (pintype "input"))
      (node (ref "U701") (pin "35") (pinfunction "INB13_3_35") (pintype "input"))
      (node (ref "U701") (pin "47") (pinfunction "INB26_1_47") (pintype "input"))
      (node (ref "U701") (pin "48") (pinfunction "INB26_2_48") (pintype "input"))
      (node (ref "U701") (pin "49") (pinfunction "INB26_3_49") (pintype "input"))
      (node (ref "U701") (pin "53") (pinfunction "VSYS_53") (pintype "power_in"))
      (node (ref "U701") (pin "56") (pinfunction "INL1_56") (pintype "input"))
    )
    (net (code "57") (name "WDOG_B") (class "Default")
      (node (ref "R710") (pin "1") (pinfunction "1_1") (pintype "passive"))
      (node (ref "TP916") (pin "1") (pinfunction "TP_1") (pintype "passive"))
    )
  )
)
